# gate_driver2b.net
KiCad netlist of a schematic drawn in EAGLE
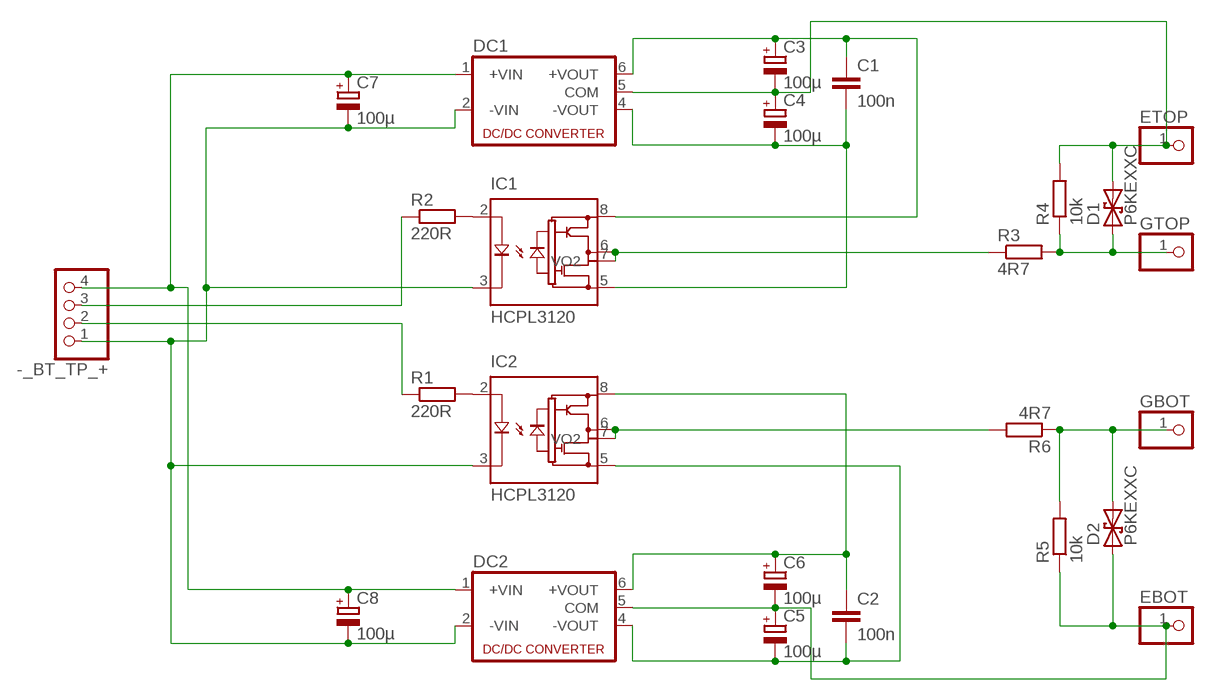
[diagram p0: schematic, sheet 1]

(export (version "E")
  (design (tool "Eeschema 10.0.6"))
  (components
    (comp (ref "-_BT_TP_+")
      (value "PINHD-1X4")
      (footprint "eagle-import:1X04")
      (libsource (lib "eagle-import") (part "PINHD-1X4"))
    )
    (comp (ref "C1")
      (value "100n")
      (footprint "eagle-import:C050-025X075")
      (libsource (lib "eagle-import") (part "C-EU050-025X075"))
    )
    (comp (ref "C2")
      (value "100n")
      (footprint "eagle-import:C050-025X075")
      (libsource (lib "eagle-import") (part "C-EU050-025X075"))
    )
    (comp (ref "C3")
      (value "100µ")
      (footprint "eagle-import:E2,5-6E")
      (libsource (lib "eagle-import") (part "CPOL-EUE2,5-6E"))
    )
    (comp (ref "C4")
      (value "100µ")
      (footprint "eagle-import:E2,5-6E")
      (libsource (lib "eagle-import") (part "CPOL-EUE2,5-6E"))
    )
    (comp (ref "C5")
      (value "100µ")
      (footprint "eagle-import:E2,5-6E")
      (libsource (lib "eagle-import") (part "CPOL-EUE2,5-6E"))
    )
    (comp (ref "C6")
      (value "100µ")
      (footprint "eagle-import:E2,5-6E")
      (libsource (lib "eagle-import") (part "CPOL-EUE2,5-6E"))
    )
    (comp (ref "C7")
      (value "100µ")
      (footprint "eagle-import:E2,5-5")
      (libsource (lib "eagle-import") (part "CPOL-EUE2.5-5"))
    )
    (comp (ref "C8")
      (value "100µ")
      (footprint "eagle-import:E2,5-5")
      (libsource (lib "eagle-import") (part "CPOL-EUE2.5-5"))
    )
    (comp (ref "D1")
      (value "P6KEXXC")
      (footprint "eagle-import:CB417-15")
      (libsource (lib "eagle-import") (part "P6KEXXC"))
    )
    (comp (ref "D2")
      (value "P6KEXXC")
      (footprint "eagle-import:CB417-15")
      (libsource (lib "eagle-import") (part "P6KEXXC"))
    )
    (comp (ref "DC1")
      (value "NMA")
      (footprint "eagle-import:NMA")
      (libsource (lib "eagle-import") (part "NMA"))
    )
    (comp (ref "DC2")
      (value "NMA")
      (footprint "eagle-import:NMA")
      (libsource (lib "eagle-import") (part "NMA"))
    )
    (comp (ref "EBOT")
      (value "PINHD-1X1")
      (footprint "eagle-import:1X01")
      (libsource (lib "eagle-import") (part "PINHD-1X1"))
    )
    (comp (ref "ETOP")
      (value "PINHD-1X1")
      (footprint "eagle-import:1X01")
      (libsource (lib "eagle-import") (part "PINHD-1X1"))
    )
    (comp (ref "GBOT")
      (value "PINHD-1X1")
      (footprint "eagle-import:1X01")
      (libsource (lib "eagle-import") (part "PINHD-1X1"))
    )
    (comp (ref "GTOP")
      (value "PINHD-1X1")
      (footprint "eagle-import:1X01")
      (libsource (lib "eagle-import") (part "PINHD-1X1"))
    )
    (comp (ref "IC1")
      (value "HCPL3120")
      (footprint "eagle-import:DIL08")
      (libsource (lib "eagle-import") (part "HCPL3120"))
    )
    (comp (ref "IC2")
      (value "HCPL3120")
      (footprint "eagle-import:DIL08")
      (libsource (lib "eagle-import") (part "HCPL3120"))
    )
    (comp (ref "R1")
      (value "220R")
      (footprint "eagle-import:0207_10")
      (libsource (lib "eagle-import") (part "R-EU_0207/10"))
    )
    (comp (ref "R2")
      (value "220R")
      (footprint "eagle-import:0207_10")
      (libsource (lib "eagle-import") (part "R-EU_0207/10"))
    )
    (comp (ref "R3")
      (value "4R7")
      (footprint "eagle-import:0309_12")
      (libsource (lib "eagle-import") (part "R-EU_0309/12"))
    )
    (comp (ref "R4")
      (value "10k")
      (footprint "eagle-import:0207_10")
      (libsource (lib "eagle-import") (part "R-EU_0207/10"))
    )
    (comp (ref "R5")
      (value "10k")
      (footprint "eagle-import:0207_10")
      (libsource (lib "eagle-import") (part "R-EU_0207/10"))
    )
    (comp (ref "R6")
      (value "4R7")
      (footprint "eagle-import:0309_12")
      (libsource (lib "eagle-import") (part "R-EU_0309/12"))
    )
  )
  (nets
    (net (code "1") (name "Net-(-_BT_TP_+-Pad2)") (class "Default")
      (node (ref "-_BT_TP_+") (pin "2") (pinfunction "2_2") (pintype "passive"))
      (node (ref "R1") (pin "1") (pinfunction "1_1") (pintype "passive"))
    )
    (net (code "2") (name "Net-(-_BT_TP_+-Pad3)") (class "Default")
      (node (ref "-_BT_TP_+") (pin "3") (pinfunction "3_3") (pintype "passive"))
      (node (ref "R2") (pin "1") (pinfunction "1_1") (pintype "passive"))
    )
    (net (code "3") (name "Net-(D1-1)") (class "Default")
      (node (ref "D1") (pin "A") (pinfunction "1_A") (pintype "passive"))
      (node (ref "GTOP") (pin "1") (pinfunction "1_1") (pintype "passive"))
      (node (ref "R3") (pin "2") (pinfunction "2_2") (pintype "passive"))
      (node (ref "R4") (pin "1") (pinfunction "1_1") (pintype "passive"))
    )
    (net (code "4") (name "Net-(D1-2)") (class "Default")
      (node (ref "C3") (pin "-") (pinfunction "-_-") (pintype "passive"))
      (node (ref "C4") (pin "+") (pinfunction "+_+") (pintype "passive"))
      (node (ref "D1") (pin "C") (pinfunction "2_C") (pintype "passive"))
      (node (ref "DC1") (pin "5") (pinfunction "COM_5") (pintype "passive"))
      (node (ref "ETOP") (pin "1") (pinfunction "1_1") (pintype "passive"))
      (node (ref "R4") (pin "2") (pinfunction "2_2") (pintype "passive"))
    )
    (net (code "5") (name "Net-(D2-1)") (class "Default")
      (node (ref "C5") (pin "+") (pinfunction "+_+") (pintype "passive"))
      (node (ref "C6") (pin "-") (pinfunction "-_-") (pintype "passive"))
      (node (ref "D2") (pin "A") (pinfunction "1_A") (pintype "passive"))
      (node (ref "DC2") (pin "5") (pinfunction "COM_5") (pintype "passive"))
      (node (ref "EBOT") (pin "1") (pinfunction "1_1") (pintype "passive"))
      (node (ref "R5") (pin "1") (pinfunction "1_1") (pintype "passive"))
    )
    (net (code "6") (name "Net-(D2-2)") (class "Default")
      (node (ref "D2") (pin "C") (pinfunction "2_C") (pintype "passive"))
      (node (ref "GBOT") (pin "1") (pinfunction "1_1") (pintype "passive"))
      (node (ref "R5") (pin "2") (pinfunction "2_2") (pintype "passive"))
      (node (ref "R6") (pin "1") (pinfunction "1_1") (pintype "passive"))
    )
    (net (code "7") (name "Net-(DC1-+VIN)") (class "Default")
      (node (ref "-_BT_TP_+") (pin "4") (pinfunction "4_4") (pintype "passive"))
      (node (ref "C7") (pin "+") (pinfunction "+_+") (pintype "passive"))
      (node (ref "C8") (pin "+") (pinfunction "+_+") (pintype "passive"))
      (node (ref "DC1") (pin "1") (pinfunction "+VIN_1") (pintype "passive"))
      (node (ref "DC2") (pin "1") (pinfunction "+VIN_1") (pintype "passive"))
    )
    (net (code "8") (name "Net-(DC1-+VOUT)") (class "Default")
      (node (ref "C1") (pin "1") (pinfunction "1_1") (pintype "passive"))
      (node (ref "C3") (pin "+") (pinfunction "+_+") (pintype "passive"))
      (node (ref "DC1") (pin "6") (pinfunction "+VOUT_6") (pintype "passive"))
      (node (ref "IC1") (pin "8") (pinfunction "VCC_8") (pintype "passive"))
    )
    (net (code "9") (name "Net-(DC1--VIN)") (class "Default")
      (node (ref "-_BT_TP_+") (pin "1") (pinfunction "1_1") (pintype "passive"))
      (node (ref "C7") (pin "-") (pinfunction "-_-") (pintype "passive"))
      (node (ref "C8") (pin "-") (pinfunction "-_-") (pintype "passive"))
      (node (ref "DC1") (pin "2") (pinfunction "-VIN_2") (pintype "passive"))
      (node (ref "DC2") (pin "2") (pinfunction "-VIN_2") (pintype "passive"))
      (node (ref "IC1") (pin "3") (pinfunction "CATHODE_3") (pintype "passive"))
      (node (ref "IC2") (pin "3") (pinfunction "CATHODE_3") (pintype "passive"))
    )
    (net (code "10") (name "Net-(DC1--VOUT)") (class "Default")
      (node (ref "C1") (pin "2") (pinfunction "2_2") (pintype "passive"))
      (node (ref "C4") (pin "-") (pinfunction "-_-") (pintype "passive"))
      (node (ref "DC1") (pin "4") (pinfunction "-VOUT_4") (pintype "passive"))
      (node (ref "IC1") (pin "5") (pinfunction "VEE_5") (pintype "passive"))
    )
    (net (code "11") (name "Net-(DC2-+VOUT)") (class "Default")
      (node (ref "C2") (pin "1") (pinfunction "1_1") (pintype "passive"))
      (node (ref "C6") (pin "+") (pinfunction "+_+") (pintype "passive"))
      (node (ref "DC2") (pin "6") (pinfunction "+VOUT_6") (pintype "passive"))
      (node (ref "IC2") (pin "8") (pinfunction "VCC_8") (pintype "passive"))
    )
    (net (code "12") (name "Net-(DC2--VOUT)") (class "Default")
      (node (ref "C2") (pin "2") (pinfunction "2_2") (pintype "passive"))
      (node (ref "C5") (pin "-") (pinfunction "-_-") (pintype "passive"))
      (node (ref "DC2") (pin "4") (pinfunction "-VOUT_4") (pintype "passive"))
      (node (ref "IC2") (pin "5") (pinfunction "VEE_5") (pintype "passive"))
    )
    (net (code "13") (name "Net-(IC1-ANODE)") (class "Default")
      (node (ref "IC1") (pin "2") (pinfunction "ANODE_2") (pintype "passive"))
      (node (ref "R2") (pin "2") (pinfunction "2_2") (pintype "passive"))
    )
    (net (code "14") (name "Net-(IC1-VO)") (class "Default")
      (node (ref "IC1") (pin "6") (pinfunction "VO_6") (pintype "passive"))
      (node (ref "IC1") (pin "7") (pinfunction "VO2_7") (pintype "bidirectional"))
      (node (ref "R3") (pin "1") (pinfunction "1_1") (pintype "passive"))
    )
    (net (code "15") (name "Net-(IC2-ANODE)") (class "Default")
      (node (ref "IC2") (pin "2") (pinfunction "ANODE_2") (pintype "passive"))
      (node (ref "R1") (pin "2") (pinfunction "2_2") (pintype "passive"))
    )
    (net (code "16") (name "Net-(IC2-VO)") (class "Default")
      (node (ref "IC2") (pin "6") (pinfunction "VO_6") (pintype "passive"))
      (node (ref "IC2") (pin "7") (pinfunction "VO2_7") (pintype "bidirectional"))
      (node (ref "R6") (pin "2") (pinfunction "2_2") (pintype "passive"))
    )
  )
)
